# jtag-isp_dapter.net
KiCad netlist of a schematic drawn in EAGLE
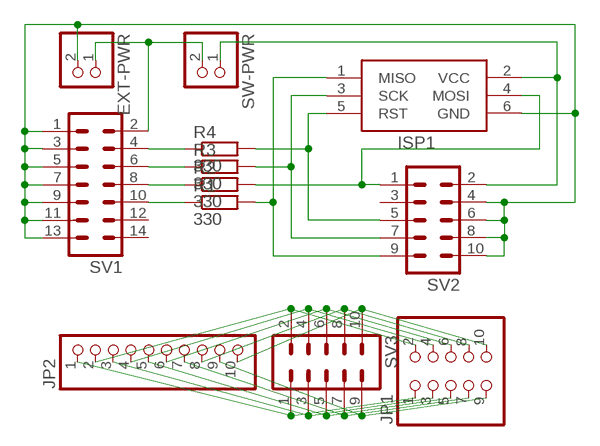
[diagram p0: schematic, sheet 1]

(export (version "E")
  (design (tool "Eeschema 10.0.6"))
  (components
    (comp (ref "EXT-PWR")
      (value "PINHD-1X2")
      (footprint "eagle-import:1X02")
      (libsource (lib "eagle-import") (part "PINHD-1X2"))
    )
    (comp (ref "ISP1")
      (value "AVRISP-6")
      (footprint "eagle-import:AVRISP")
      (libsource (lib "eagle-import") (part "AVRISP-6"))
    )
    (comp (ref "JP1")
      (value "PINHD-2X5")
      (footprint "eagle-import:2X05")
      (libsource (lib "eagle-import") (part "PINHD-2X5"))
    )
    (comp (ref "JP2")
      (value "PINHD-1X10")
      (footprint "eagle-import:1X10")
      (libsource (lib "eagle-import") (part "PINHD-1X10"))
    )
    (comp (ref "R1")
      (value "330")
      (footprint "eagle-import:0204_7")
      (libsource (lib "eagle-import") (part "R-EU_0204/7"))
    )
    (comp (ref "R2")
      (value "330")
      (footprint "eagle-import:0204_7")
      (libsource (lib "eagle-import") (part "R-EU_0204/7"))
    )
    (comp (ref "R3")
      (value "330")
      (footprint "eagle-import:0204_7")
      (libsource (lib "eagle-import") (part "R-EU_0204/7"))
    )
    (comp (ref "R4")
      (value "330")
      (footprint "eagle-import:0204_7")
      (libsource (lib "eagle-import") (part "R-EU_0204/7"))
    )
    (comp (ref "SV1")
      (value "ML14")
      (footprint "eagle-import:ML14")
      (libsource (lib "eagle-import") (part "ML14"))
    )
    (comp (ref "SV2")
      (value "ML10")
      (footprint "eagle-import:ML10")
      (libsource (lib "eagle-import") (part "ML10"))
    )
    (comp (ref "SV3")
      (value "ML10")
      (footprint "eagle-import:ML10")
      (libsource (lib "eagle-import") (part "ML10"))
    )
    (comp (ref "SW-PWR")
      (value "PINHD-1X2")
      (footprint "eagle-import:1X02")
      (libsource (lib "eagle-import") (part "PINHD-1X2"))
    )
  )
  (nets
    (net (code "1") (name "Net-(EXT-PWR-Pad1)") (class "Default")
      (node (ref "EXT-PWR") (pin "1") (pinfunction "1_1") (pintype "passive"))
      (node (ref "SV1") (pin "2") (pinfunction "2_2") (pintype "passive"))
      (node (ref "SW-PWR") (pin "2") (pinfunction "2_2") (pintype "passive"))
    )
    (net (code "2") (name "Net-(ISP1-GND)") (class "Default")
      (node (ref "EXT-PWR") (pin "2") (pinfunction "2_2") (pintype "passive"))
      (node (ref "ISP1") (pin "6") (pinfunction "GND_6") (pintype "power_in"))
      (node (ref "SV1") (pin "1") (pinfunction "1_1") (pintype "passive"))
      (node (ref "SV1") (pin "11") (pinfunction "11_11") (pintype "passive"))
      (node (ref "SV1") (pin "13") (pinfunction "13_13") (pintype "passive"))
      (node (ref "SV1") (pin "3") (pinfunction "3_3") (pintype "passive"))
      (node (ref "SV1") (pin "5") (pinfunction "5_5") (pintype "passive"))
      (node (ref "SV1") (pin "7") (pinfunction "7_7") (pintype "passive"))
      (node (ref "SV1") (pin "9") (pinfunction "9_9") (pintype "passive"))
      (node (ref "SV2") (pin "10") (pinfunction "10_10") (pintype "passive"))
      (node (ref "SV2") (pin "4") (pinfunction "4_4") (pintype "passive"))
      (node (ref "SV2") (pin "6") (pinfunction "6_6") (pintype "passive"))
      (node (ref "SV2") (pin "8") (pinfunction "8_8") (pintype "passive"))
    )
    (net (code "3") (name "Net-(ISP1-MISO)") (class "Default")
      (node (ref "ISP1") (pin "1") (pinfunction "MISO_1") (pintype "input"))
      (node (ref "R1") (pin "2") (pinfunction "2_2") (pintype "passive"))
      (node (ref "SV2") (pin "9") (pinfunction "9_9") (pintype "passive"))
    )
    (net (code "4") (name "Net-(ISP1-MOSI)") (class "Default")
      (node (ref "ISP1") (pin "4") (pinfunction "MOSI_4") (pintype "output"))
      (node (ref "R2") (pin "2") (pinfunction "2_2") (pintype "passive"))
      (node (ref "SV2") (pin "1") (pinfunction "1_1") (pintype "passive"))
    )
    (net (code "5") (name "Net-(ISP1-RST)") (class "Default")
      (node (ref "ISP1") (pin "5") (pinfunction "RST_5") (pintype "output"))
      (node (ref "R4") (pin "2") (pinfunction "2_2") (pintype "passive"))
      (node (ref "SV2") (pin "5") (pinfunction "5_5") (pintype "passive"))
    )
    (net (code "6") (name "Net-(ISP1-SCK)") (class "Default")
      (node (ref "ISP1") (pin "3") (pinfunction "SCK_3") (pintype "output"))
      (node (ref "R3") (pin "2") (pinfunction "2_2") (pintype "passive"))
      (node (ref "SV2") (pin "7") (pinfunction "7_7") (pintype "passive"))
    )
    (net (code "7") (name "Net-(ISP1-VCC)") (class "Default")
      (node (ref "ISP1") (pin "2") (pinfunction "VCC_2") (pintype "power_in"))
      (node (ref "SV2") (pin "2") (pinfunction "2_2") (pintype "passive"))
      (node (ref "SW-PWR") (pin "1") (pinfunction "1_1") (pintype "passive"))
    )
    (net (code "8") (name "Net-(JP1-Pad1)") (class "Default")
      (node (ref "JP1") (pin "1") (pinfunction "1_1") (pintype "passive"))
      (node (ref "JP2") (pin "1") (pinfunction "1_1") (pintype "passive"))
      (node (ref "SV3") (pin "1") (pinfunction "1_1") (pintype "passive"))
    )
    (net (code "9") (name "Net-(JP1-Pad2)") (class "Default")
      (node (ref "JP1") (pin "2") (pinfunction "2_2") (pintype "passive"))
      (node (ref "JP2") (pin "2") (pinfunction "2_2") (pintype "passive"))
      (node (ref "SV3") (pin "2") (pinfunction "2_2") (pintype "passive"))
    )
    (net (code "10") (name "Net-(JP1-Pad3)") (class "Default")
      (node (ref "JP1") (pin "3") (pinfunction "3_3") (pintype "passive"))
      (node (ref "JP2") (pin "3") (pinfunction "3_3") (pintype "passive"))
      (node (ref "SV3") (pin "3") (pinfunction "3_3") (pintype "passive"))
    )
    (net (code "11") (name "Net-(JP1-Pad4)") (class "Default")
      (node (ref "JP1") (pin "4") (pinfunction "4_4") (pintype "passive"))
      (node (ref "JP2") (pin "4") (pinfunction "4_4") (pintype "passive"))
      (node (ref "SV3") (pin "4") (pinfunction "4_4") (pintype "passive"))
    )
    (net (code "12") (name "Net-(JP1-Pad5)") (class "Default")
      (node (ref "JP1") (pin "5") (pinfunction "5_5") (pintype "passive"))
      (node (ref "JP2") (pin "5") (pinfunction "5_5") (pintype "passive"))
      (node (ref "SV3") (pin "5") (pinfunction "5_5") (pintype "passive"))
    )
    (net (code "13") (name "Net-(JP1-Pad6)") (class "Default")
      (node (ref "JP1") (pin "6") (pinfunction "6_6") (pintype "passive"))
      (node (ref "JP2") (pin "6") (pinfunction "6_6") (pintype "passive"))
      (node (ref "SV3") (pin "6") (pinfunction "6_6") (pintype "passive"))
    )
    (net (code "14") (name "Net-(JP1-Pad7)") (class "Default")
      (node (ref "JP1") (pin "7") (pinfunction "7_7") (pintype "passive"))
      (node (ref "JP2") (pin "7") (pinfunction "7_7") (pintype "passive"))
      (node (ref "SV3") (pin "7") (pinfunction "7_7") (pintype "passive"))
    )
    (net (code "15") (name "Net-(JP1-Pad8)") (class "Default")
      (node (ref "JP1") (pin "8") (pinfunction "8_8") (pintype "passive"))
      (node (ref "JP2") (pin "8") (pinfunction "8_8") (pintype "passive"))
      (node (ref "SV3") (pin "8") (pinfunction "8_8") (pintype "passive"))
    )
    (net (code "16") (name "Net-(JP1-Pad9)") (class "Default")
      (node (ref "JP1") (pin "9") (pinfunction "9_9") (pintype "passive"))
      (node (ref "JP2") (pin "9") (pinfunction "9_9") (pintype "passive"))
      (node (ref "SV3") (pin "9") (pinfunction "9_9") (pintype "passive"))
    )
    (net (code "17") (name "Net-(JP1-Pad10)") (class "Default")
      (node (ref "JP1") (pin "10") (pinfunction "10_10") (pintype "passive"))
      (node (ref "JP2") (pin "10") (pinfunction "10_10") (pintype "passive"))
      (node (ref "SV3") (pin "10") (pinfunction "10_10") (pintype "passive"))
    )
    (net (code "18") (name "Net-(R1-Pad1)") (class "Default")
      (node (ref "R1") (pin "1") (pinfunction "1_1") (pintype "passive"))
      (node (ref "SV1") (pin "10") (pinfunction "10_10") (pintype "passive"))
    )
    (net (code "19") (name "Net-(R2-Pad1)") (class "Default")
      (node (ref "R2") (pin "1") (pinfunction "1_1") (pintype "passive"))
      (node (ref "SV1") (pin "8") (pinfunction "8_8") (pintype "passive"))
    )
    (net (code "20") (name "Net-(R3-Pad1)") (class "Default")
      (node (ref "R3") (pin "1") (pinfunction "1_1") (pintype "passive"))
      (node (ref "SV1") (pin "6") (pinfunction "6_6") (pintype "passive"))
    )
    (net (code "21") (name "Net-(R4-Pad1)") (class "Default")
      (node (ref "R4") (pin "1") (pinfunction "1_1") (pintype "passive"))
      (node (ref "SV1") (pin "4") (pinfunction "4_4") (pintype "passive"))
    )
    (net (code "22") (name "unconnected-(SV1-Pad12)") (class "Default")
      (node (ref "SV1") (pin "12") (pinfunction "12_12") (pintype "passive"))
    )
    (net (code "23") (name "unconnected-(SV1-Pad14)") (class "Default")
      (node (ref "SV1") (pin "14") (pinfunction "14_14") (pintype "passive"))
    )
    (net (code "24") (name "unconnected-(SV2-Pad3)") (class "Default")
      (node (ref "SV2") (pin "3") (pinfunction "3_3") (pintype "passive"))
    )
  )
)
